# VGA-OSCI.net
KiCad netlist of a schematic drawn in EAGLE
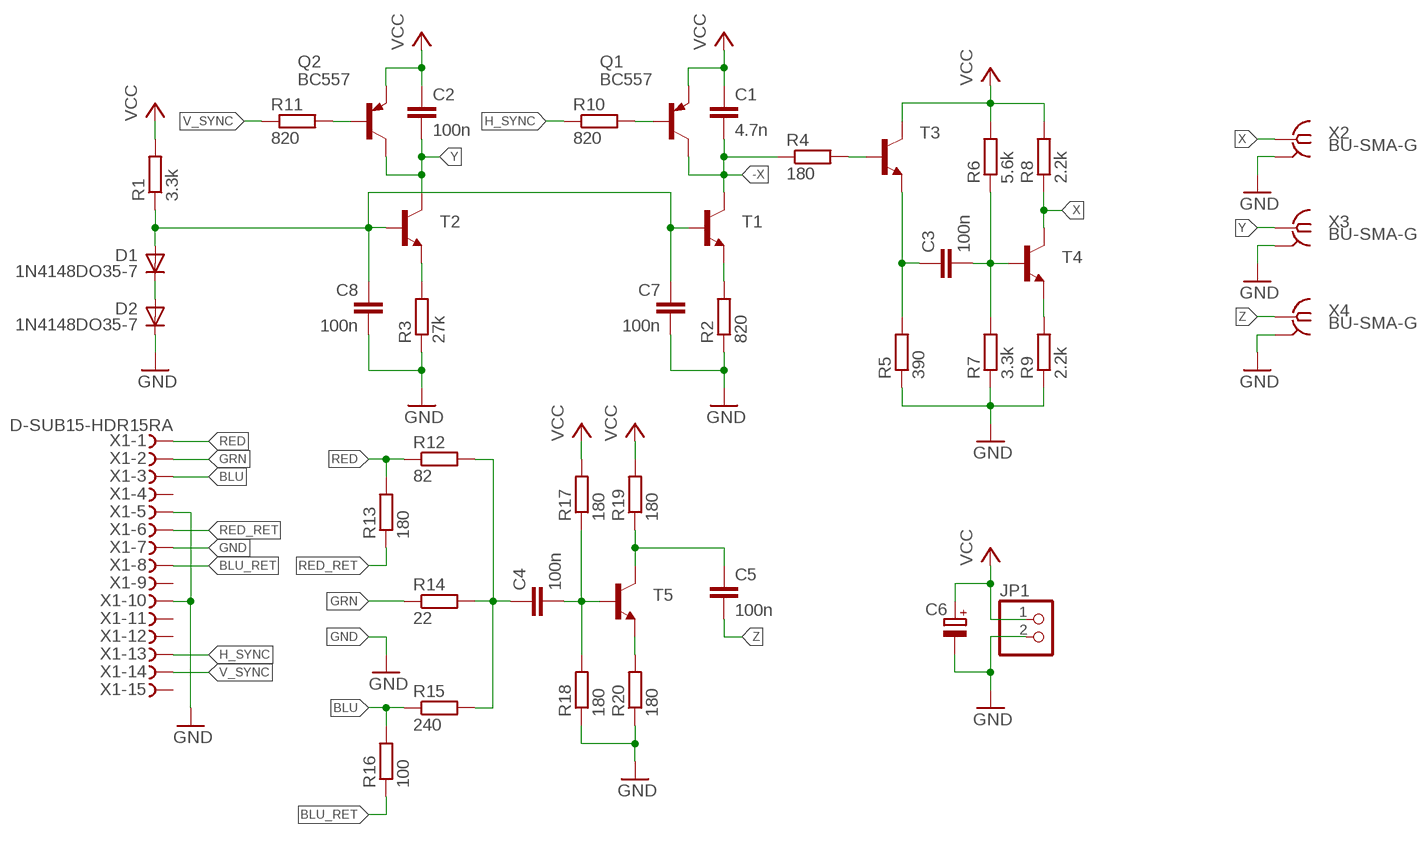
[diagram p0: schematic, sheet 1]

(export (version "E")
  (design (tool "Eeschema 10.0.6"))
  (components
    (comp (ref "C1")
      (value "4.7n")
      (footprint "eagle-import:C050-024X044")
      (libsource (lib "eagle-import") (part "C-EU050-024X044"))
    )
    (comp (ref "C2")
      (value "100n")
      (footprint "eagle-import:C050-024X044")
      (libsource (lib "eagle-import") (part "C-EU050-024X044"))
    )
    (comp (ref "C3")
      (value "100n")
      (footprint "eagle-import:C050-024X044")
      (libsource (lib "eagle-import") (part "C-EU050-024X044"))
    )
    (comp (ref "C4")
      (value "100n")
      (footprint "eagle-import:C050-024X044")
      (libsource (lib "eagle-import") (part "C-EU050-024X044"))
    )
    (comp (ref "C5")
      (value "100n")
      (footprint "eagle-import:C050-024X044")
      (libsource (lib "eagle-import") (part "C-EU050-024X044"))
    )
    (comp (ref "C6")
      (value "CPOL-EUB45181A")
      (footprint "eagle-import:B45181A")
      (libsource (lib "eagle-import") (part "CPOL-EUB45181A"))
    )
    (comp (ref "C7")
      (value "100n")
      (footprint "eagle-import:C050-024X044")
      (libsource (lib "eagle-import") (part "C-EU050-024X044"))
    )
    (comp (ref "C8")
      (value "100n")
      (footprint "eagle-import:C050-024X044")
      (libsource (lib "eagle-import") (part "C-EU050-024X044"))
    )
    (comp (ref "D1")
      (value "1N4148DO35-7")
      (footprint "eagle-import:DO35-7")
      (libsource (lib "eagle-import") (part "1N4148DO35-7"))
    )
    (comp (ref "D2")
      (value "1N4148DO35-7")
      (footprint "eagle-import:DO35-7")
      (libsource (lib "eagle-import") (part "1N4148DO35-7"))
    )
    (comp (ref "JP1")
      (value "PINHD-1X2")
      (footprint "eagle-import:1X02")
      (libsource (lib "eagle-import") (part "PINHD-1X2"))
    )
    (comp (ref "Q1")
      (value "BC557")
      (footprint "eagle-import:TO92-EBC")
      (libsource (lib "eagle-import") (part "BC557"))
    )
    (comp (ref "Q2")
      (value "BC557")
      (footprint "eagle-import:TO92-EBC")
      (libsource (lib "eagle-import") (part "BC557"))
    )
    (comp (ref "R1")
      (value "3.3k")
      (footprint "eagle-import:0204_7")
      (libsource (lib "eagle-import") (part "R-EU_0204/7"))
    )
    (comp (ref "R2")
      (value "820")
      (footprint "eagle-import:0204_7")
      (libsource (lib "eagle-import") (part "R-EU_0204/7"))
    )
    (comp (ref "R3")
      (value "27k")
      (footprint "eagle-import:0204_7")
      (libsource (lib "eagle-import") (part "R-EU_0204/7"))
    )
    (comp (ref "R4")
      (value "180")
      (footprint "eagle-import:0204_7")
      (libsource (lib "eagle-import") (part "R-EU_0204/7"))
    )
    (comp (ref "R5")
      (value "390")
      (footprint "eagle-import:0204_7")
      (libsource (lib "eagle-import") (part "R-EU_0204/7"))
    )
    (comp (ref "R6")
      (value "5.6k")
      (footprint "eagle-import:0204_7")
      (libsource (lib "eagle-import") (part "R-EU_0204/7"))
    )
    (comp (ref "R7")
      (value "3.3k")
      (footprint "eagle-import:0204_7")
      (libsource (lib "eagle-import") (part "R-EU_0204/7"))
    )
    (comp (ref "R8")
      (value "2.2k")
      (footprint "eagle-import:0204_7")
      (libsource (lib "eagle-import") (part "R-EU_0204/7"))
    )
    (comp (ref "R9")
      (value "2.2k")
      (footprint "eagle-import:0204_7")
      (libsource (lib "eagle-import") (part "R-EU_0204/7"))
    )
    (comp (ref "R10")
      (value "820")
      (footprint "eagle-import:0204_7")
      (libsource (lib "eagle-import") (part "R-EU_0204/7"))
    )
    (comp (ref "R11")
      (value "820")
      (footprint "eagle-import:0204_7")
      (libsource (lib "eagle-import") (part "R-EU_0204/7"))
    )
    (comp (ref "R12")
      (value "82")
      (footprint "eagle-import:0204_7")
      (libsource (lib "eagle-import") (part "R-EU_0204/7"))
    )
    (comp (ref "R13")
      (value "180")
      (footprint "eagle-import:0204_7")
      (libsource (lib "eagle-import") (part "R-EU_0204/7"))
    )
    (comp (ref "R14")
      (value "22")
      (footprint "eagle-import:0204_7")
      (libsource (lib "eagle-import") (part "R-EU_0204/7"))
    )
    (comp (ref "R15")
      (value "240")
      (footprint "eagle-import:0204_7")
      (libsource (lib "eagle-import") (part "R-EU_0204/7"))
    )
    (comp (ref "R16")
      (value "100")
      (footprint "eagle-import:0204_7")
      (libsource (lib "eagle-import") (part "R-EU_0204/7"))
    )
    (comp (ref "R17")
      (value "180")
      (footprint "eagle-import:0204_7")
      (libsource (lib "eagle-import") (part "R-EU_0204/7"))
    )
    (comp (ref "R18")
      (value "180")
      (footprint "eagle-import:0204_7")
      (libsource (lib "eagle-import") (part "R-EU_0204/7"))
    )
    (comp (ref "R19")
      (value "180")
      (footprint "eagle-import:0204_7")
      (libsource (lib "eagle-import") (part "R-EU_0204/7"))
    )
    (comp (ref "R20")
      (value "180")
      (footprint "eagle-import:0204_7")
      (libsource (lib "eagle-import") (part "R-EU_0204/7"))
    )
    (comp (ref "T1")
      (value "BC547-NPN-TO92-CBE")
      (footprint "eagle-import:TO92-CBE")
      (libsource (lib "eagle-import") (part "-NPN-TO92-CBEBC547"))
    )
    (comp (ref "T2")
      (value "BC547-NPN-TO92-CBE")
      (footprint "eagle-import:TO92-CBE")
      (libsource (lib "eagle-import") (part "-NPN-TO92-CBEBC547"))
    )
    (comp (ref "T3")
      (value "BC547-NPN-TO92-CBE")
      (footprint "eagle-import:TO92-CBE")
      (libsource (lib "eagle-import") (part "-NPN-TO92-CBEBC547"))
    )
    (comp (ref "T4")
      (value "BC547-NPN-TO92-CBE")
      (footprint "eagle-import:TO92-CBE")
      (libsource (lib "eagle-import") (part "-NPN-TO92-CBEBC547"))
    )
    (comp (ref "T5")
      (value "BC547-NPN-TO92-CBE")
      (footprint "eagle-import:TO92-CBE")
      (libsource (lib "eagle-import") (part "-NPN-TO92-CBEBC547"))
    )
    (comp (ref "X1")
      (value "D-SUB15-HDR15RA")
      (footprint "eagle-import:HDR15RA")
      (libsource (lib "eagle-import") (part "D-SUB15-HDR15RA"))
    )
    (comp (ref "X2")
      (value "BU-SMA-G")
      (footprint "eagle-import:BU-SMA-G")
      (libsource (lib "eagle-import") (part "BU-SMA-G"))
    )
    (comp (ref "X3")
      (value "BU-SMA-G")
      (footprint "eagle-import:BU-SMA-G")
      (libsource (lib "eagle-import") (part "BU-SMA-G"))
    )
    (comp (ref "X4")
      (value "BU-SMA-G")
      (footprint "eagle-import:BU-SMA-G")
      (libsource (lib "eagle-import") (part "BU-SMA-G"))
    )
  )
  (nets
    (net (code "1") (name "-X") (class "Default")
      (node (ref "C1") (pin "2") (pinfunction "2_2") (pintype "passive"))
      (node (ref "Q1") (pin "C") (pinfunction "C_C") (pintype "passive"))
      (node (ref "R4") (pin "1") (pinfunction "1_1") (pintype "passive"))
      (node (ref "T1") (pin "C") (pinfunction "C_C") (pintype "passive"))
    )
    (net (code "2") (name "BLU") (class "Default")
      (node (ref "R15") (pin "1") (pinfunction "1_1") (pintype "passive"))
      (node (ref "R16") (pin "2") (pinfunction "2_2") (pintype "passive"))
      (node (ref "X1") (pin "3") (pinfunction "F_3") (pintype "passive"))
    )
    (net (code "3") (name "BLU_RET") (class "Default")
      (node (ref "R16") (pin "1") (pinfunction "1_1") (pintype "passive"))
      (node (ref "X1") (pin "8") (pinfunction "F_8") (pintype "passive"))
    )
    (net (code "4") (name "GND") (class "Default")
      (node (ref "C6") (pin "-") (pinfunction "-_-") (pintype "passive"))
      (node (ref "C7") (pin "2") (pinfunction "2_2") (pintype "passive"))
      (node (ref "C8") (pin "2") (pinfunction "2_2") (pintype "passive"))
      (node (ref "D2") (pin "C") (pinfunction "C_C") (pintype "passive"))
      (node (ref "JP1") (pin "2") (pinfunction "2_2") (pintype "passive"))
      (node (ref "R18") (pin "1") (pinfunction "1_1") (pintype "passive"))
      (node (ref "R2") (pin "1") (pinfunction "1_1") (pintype "passive"))
      (node (ref "R20") (pin "1") (pinfunction "1_1") (pintype "passive"))
      (node (ref "R3") (pin "1") (pinfunction "1_1") (pintype "passive"))
      (node (ref "R5") (pin "1") (pinfunction "1_1") (pintype "passive"))
      (node (ref "R7") (pin "1") (pinfunction "1_1") (pintype "passive"))
      (node (ref "R9") (pin "1") (pinfunction "1_1") (pintype "passive"))
      (node (ref "X1") (pin "10") (pinfunction "F_10") (pintype "passive"))
      (node (ref "X1") (pin "5") (pinfunction "F_5") (pintype "passive"))
      (node (ref "X1") (pin "7") (pinfunction "F_7") (pintype "passive"))
      (node (ref "X2") (pin "2") (pinfunction "2_2") (pintype "passive"))
      (node (ref "X2") (pin "3") (pinfunction "2_3") (pintype "passive"))
      (node (ref "X2") (pin "4") (pinfunction "2_4") (pintype "passive"))
      (node (ref "X2") (pin "5") (pinfunction "2_5") (pintype "passive"))
      (node (ref "X3") (pin "2") (pinfunction "2_2") (pintype "passive"))
      (node (ref "X3") (pin "3") (pinfunction "2_3") (pintype "passive"))
      (node (ref "X3") (pin "4") (pinfunction "2_4") (pintype "passive"))
      (node (ref "X3") (pin "5") (pinfunction "2_5") (pintype "passive"))
      (node (ref "X4") (pin "2") (pinfunction "2_2") (pintype "passive"))
      (node (ref "X4") (pin "3") (pinfunction "2_3") (pintype "passive"))
      (node (ref "X4") (pin "4") (pinfunction "2_4") (pintype "passive"))
      (node (ref "X4") (pin "5") (pinfunction "2_5") (pintype "passive"))
    )
    (net (code "5") (name "GRN") (class "Default")
      (node (ref "R14") (pin "1") (pinfunction "1_1") (pintype "passive"))
      (node (ref "X1") (pin "2") (pinfunction "F_2") (pintype "passive"))
    )
    (net (code "6") (name "H_SYNC") (class "Default")
      (node (ref "R10") (pin "1") (pinfunction "1_1") (pintype "passive"))
      (node (ref "X1") (pin "13") (pinfunction "F_13") (pintype "passive"))
    )
    (net (code "7") (name "Net-(C3-Pad1)") (class "Default")
      (node (ref "C3") (pin "1") (pinfunction "1_1") (pintype "passive"))
      (node (ref "R5") (pin "2") (pinfunction "2_2") (pintype "passive"))
      (node (ref "T3") (pin "E") (pinfunction "E_E") (pintype "passive"))
    )
    (net (code "8") (name "Net-(C3-Pad2)") (class "Default")
      (node (ref "C3") (pin "2") (pinfunction "2_2") (pintype "passive"))
      (node (ref "R6") (pin "1") (pinfunction "1_1") (pintype "passive"))
      (node (ref "R7") (pin "2") (pinfunction "2_2") (pintype "passive"))
      (node (ref "T4") (pin "B") (pinfunction "B_B") (pintype "passive"))
    )
    (net (code "9") (name "Net-(C4-Pad1)") (class "Default")
      (node (ref "C4") (pin "1") (pinfunction "1_1") (pintype "passive"))
      (node (ref "R12") (pin "2") (pinfunction "2_2") (pintype "passive"))
      (node (ref "R14") (pin "2") (pinfunction "2_2") (pintype "passive"))
      (node (ref "R15") (pin "2") (pinfunction "2_2") (pintype "passive"))
    )
    (net (code "10") (name "Net-(C4-Pad2)") (class "Default")
      (node (ref "C4") (pin "2") (pinfunction "2_2") (pintype "passive"))
      (node (ref "R17") (pin "1") (pinfunction "1_1") (pintype "passive"))
      (node (ref "R18") (pin "2") (pinfunction "2_2") (pintype "passive"))
      (node (ref "T5") (pin "B") (pinfunction "B_B") (pintype "passive"))
    )
    (net (code "11") (name "Net-(C5-Pad1)") (class "Default")
      (node (ref "C5") (pin "1") (pinfunction "1_1") (pintype "passive"))
      (node (ref "R19") (pin "1") (pinfunction "1_1") (pintype "passive"))
      (node (ref "T5") (pin "C") (pinfunction "C_C") (pintype "passive"))
    )
    (net (code "12") (name "Net-(C7-Pad1)") (class "Default")
      (node (ref "C7") (pin "1") (pinfunction "1_1") (pintype "passive"))
      (node (ref "C8") (pin "1") (pinfunction "1_1") (pintype "passive"))
      (node (ref "D1") (pin "A") (pinfunction "A_A") (pintype "passive"))
      (node (ref "R1") (pin "1") (pinfunction "1_1") (pintype "passive"))
      (node (ref "T1") (pin "B") (pinfunction "B_B") (pintype "passive"))
      (node (ref "T2") (pin "B") (pinfunction "B_B") (pintype "passive"))
    )
    (net (code "13") (name "Net-(D1-PadC)") (class "Default")
      (node (ref "D1") (pin "C") (pinfunction "C_C") (pintype "passive"))
      (node (ref "D2") (pin "A") (pinfunction "A_A") (pintype "passive"))
    )
    (net (code "14") (name "Net-(Q1-PadB)") (class "Default")
      (node (ref "Q1") (pin "B") (pinfunction "B_B") (pintype "passive"))
      (node (ref "R10") (pin "2") (pinfunction "2_2") (pintype "passive"))
    )
    (net (code "15") (name "Net-(Q2-PadB)") (class "Default")
      (node (ref "Q2") (pin "B") (pinfunction "B_B") (pintype "passive"))
      (node (ref "R11") (pin "2") (pinfunction "2_2") (pintype "passive"))
    )
    (net (code "16") (name "Net-(R2-Pad2)") (class "Default")
      (node (ref "R2") (pin "2") (pinfunction "2_2") (pintype "passive"))
      (node (ref "T1") (pin "E") (pinfunction "E_E") (pintype "passive"))
    )
    (net (code "17") (name "Net-(R3-Pad2)") (class "Default")
      (node (ref "R3") (pin "2") (pinfunction "2_2") (pintype "passive"))
      (node (ref "T2") (pin "E") (pinfunction "E_E") (pintype "passive"))
    )
    (net (code "18") (name "Net-(R4-Pad2)") (class "Default")
      (node (ref "R4") (pin "2") (pinfunction "2_2") (pintype "passive"))
      (node (ref "T3") (pin "B") (pinfunction "B_B") (pintype "passive"))
    )
    (net (code "19") (name "Net-(R9-Pad2)") (class "Default")
      (node (ref "R9") (pin "2") (pinfunction "2_2") (pintype "passive"))
      (node (ref "T4") (pin "E") (pinfunction "E_E") (pintype "passive"))
    )
    (net (code "20") (name "Net-(R20-Pad2)") (class "Default")
      (node (ref "R20") (pin "2") (pinfunction "2_2") (pintype "passive"))
      (node (ref "T5") (pin "E") (pinfunction "E_E") (pintype "passive"))
    )
    (net (code "21") (name "RED") (class "Default")
      (node (ref "R12") (pin "1") (pinfunction "1_1") (pintype "passive"))
      (node (ref "R13") (pin "2") (pinfunction "2_2") (pintype "passive"))
      (node (ref "X1") (pin "1") (pinfunction "F_1") (pintype "passive"))
    )
    (net (code "22") (name "RED_RET") (class "Default")
      (node (ref "R13") (pin "1") (pinfunction "1_1") (pintype "passive"))
      (node (ref "X1") (pin "6") (pinfunction "F_6") (pintype "passive"))
    )
    (net (code "23") (name "VCC") (class "Default")
      (node (ref "C1") (pin "1") (pinfunction "1_1") (pintype "passive"))
      (node (ref "C2") (pin "1") (pinfunction "1_1") (pintype "passive"))
      (node (ref "C6") (pin "+") (pinfunction "+_+") (pintype "passive"))
      (node (ref "JP1") (pin "1") (pinfunction "1_1") (pintype "passive"))
      (node (ref "Q1") (pin "E") (pinfunction "E_E") (pintype "passive"))
      (node (ref "Q2") (pin "E") (pinfunction "E_E") (pintype "passive"))
      (node (ref "R1") (pin "2") (pinfunction "2_2") (pintype "passive"))
      (node (ref "R17") (pin "2") (pinfunction "2_2") (pintype "passive"))
      (node (ref "R19") (pin "2") (pinfunction "2_2") (pintype "passive"))
      (node (ref "R6") (pin "2") (pinfunction "2_2") (pintype "passive"))
      (node (ref "R8") (pin "2") (pinfunction "2_2") (pintype "passive"))
      (node (ref "T3") (pin "C") (pinfunction "C_C") (pintype "passive"))
    )
    (net (code "24") (name "V_SYNC") (class "Default")
      (node (ref "R11") (pin "1") (pinfunction "1_1") (pintype "passive"))
      (node (ref "X1") (pin "14") (pinfunction "F_14") (pintype "passive"))
    )
    (net (code "25") (name "X") (class "Default")
      (node (ref "R8") (pin "1") (pinfunction "1_1") (pintype "passive"))
      (node (ref "T4") (pin "C") (pinfunction "C_C") (pintype "passive"))
      (node (ref "X2") (pin "1") (pinfunction "1_1") (pintype "passive"))
    )
    (net (code "26") (name "Y") (class "Default")
      (node (ref "C2") (pin "2") (pinfunction "2_2") (pintype "passive"))
      (node (ref "Q2") (pin "C") (pinfunction "C_C") (pintype "passive"))
      (node (ref "T2") (pin "C") (pinfunction "C_C") (pintype "passive"))
      (node (ref "X3") (pin "1") (pinfunction "1_1") (pintype "passive"))
    )
    (net (code "27") (name "Z") (class "Default")
      (node (ref "C5") (pin "2") (pinfunction "2_2") (pintype "passive"))
      (node (ref "X4") (pin "1") (pinfunction "1_1") (pintype "passive"))
    )
    (net (code "28") (name "unconnected-(X1C-F-Pad11)") (class "Default")
      (node (ref "X1") (pin "11") (pinfunction "F_11") (pintype "passive"))
    )
    (net (code "29") (name "unconnected-(X1D-F-Pad12)") (class "Default")
      (node (ref "X1") (pin "12") (pinfunction "F_12") (pintype "passive"))
    )
    (net (code "30") (name "unconnected-(X1G-F-Pad15)") (class "Default")
      (node (ref "X1") (pin "15") (pinfunction "F_15") (pintype "passive"))
    )
    (net (code "31") (name "unconnected-(X1J-F-Pad4)") (class "Default")
      (node (ref "X1") (pin "4") (pinfunction "F_4") (pintype "passive"))
    )
    (net (code "32") (name "unconnected-(X1O-F-Pad9)") (class "Default")
      (node (ref "X1") (pin "9") (pinfunction "F_9") (pintype "passive"))
    )
  )
)
